# MainBoard.net
KiCad netlist of a schematic drawn in EAGLE
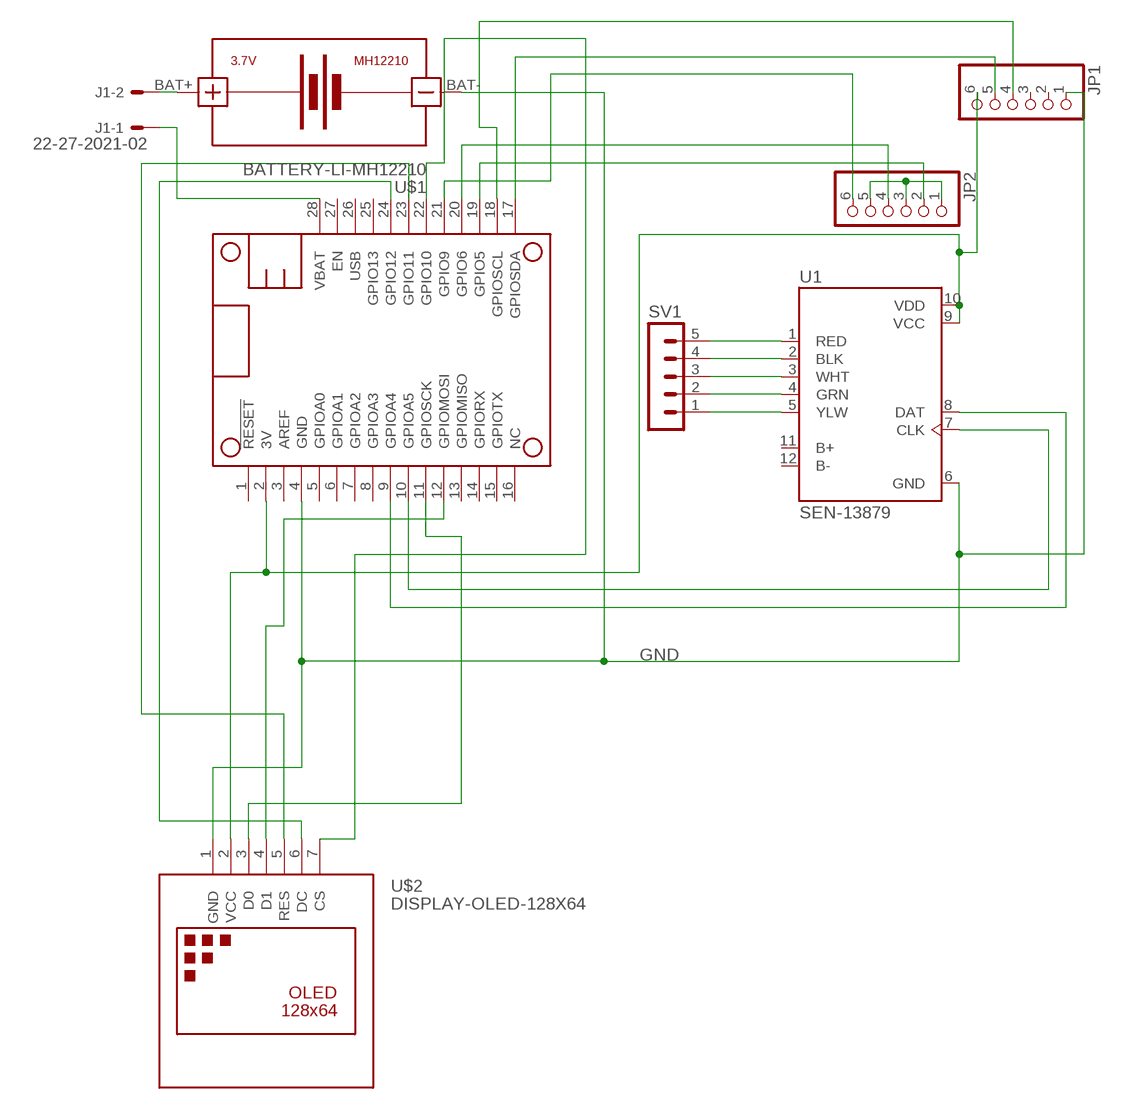
[diagram p0: schematic, sheet 1]

(export (version "E")
  (design (tool "Eeschema 10.0.6"))
  (components
    (comp (ref "J1")
      (value "22-27-2021-02")
      (footprint "eagle-import:6410-02")
      (fields (field (name "MF") "MOLEX"))
      (libsource (lib "eagle-import") (part "22-?-0227-2021"))
    )
    (comp (ref "JP1")
      (value "PINHD-1X6")
      (footprint "eagle-import:1X06")
      (libsource (lib "eagle-import") (part "PINHD-1X6"))
    )
    (comp (ref "JP2")
      (value "PINHD-1X6")
      (footprint "eagle-import:1X06")
      (libsource (lib "eagle-import") (part "PINHD-1X6"))
    )
    (comp (ref "MS1")
      (value "FEATHERWING_NODIM")
      (footprint "eagle-import:FEATHERWING_DIM")
      (libsource (lib "eagle-import") (part "FEATHERWING_NODIM"))
    )
    (comp (ref "SV1")
      (value "MA05-1")
      (footprint "eagle-import:MA05-1")
      (libsource (lib "eagle-import") (part "MA05-1"))
    )
    (comp (ref "U$1")
      (value "BATTERY-LI-MH12210")
      (footprint "eagle-import:BATTERY-LI-MH12210")
      (libsource (lib "eagle-import") (part "BATTERY-LI-MH12210"))
    )
    (comp (ref "U$2")
      (value "DISPLAY-OLED-128X64")
      (footprint "eagle-import:DISPLAY-OLED-128X64")
      (libsource (lib "eagle-import") (part "DISPLAY-OLED-128X64"))
    )
    (comp (ref "U1")
      (value "SEN-13879")
      (footprint "eagle-import:SPARKFUN_SEN-13879")
      (fields (field (name "MF") "SparkFun"))
      (libsource (lib "eagle-import") (part "SEN-13879"))
    )
  )
  (nets
    (net (code "1") (name "/GND") (class "Default")
      (node (ref "JP1") (pin "1") (pinfunction "1_1") (pintype "passive"))
      (node (ref "MS1") (pin "4") (pinfunction "GND_4") (pintype "power_in"))
      (node (ref "U$1") (pin "BAT-") (pinfunction "BAT-_BAT-") (pintype "power_in"))
      (node (ref "U$2") (pin "1") (pinfunction "GND_1") (pintype "power_in"))
      (node (ref "U1") (pin "6") (pinfunction "GND_6") (pintype "power_in"))
    )
    (net (code "2") (name "/USB") (class "Default")
      (node (ref "MS1") (pin "26") (pinfunction "USB_26") (pintype "power_in"))
    )
    (net (code "3") (name "Net-(J1A-S)") (class "Default")
      (node (ref "J1") (pin "1") (pinfunction "S_1") (pintype "passive"))
      (node (ref "MS1") (pin "28") (pinfunction "VBAT_28") (pintype "power_in"))
    )
    (net (code "4") (name "Net-(J1B-S)") (class "Default")
      (node (ref "J1") (pin "2") (pinfunction "S_2") (pintype "passive"))
      (node (ref "U$1") (pin "BAT+") (pinfunction "BAT+_BAT+") (pintype "power_in"))
    )
    (net (code "5") (name "Net-(JP2-Pad1)") (class "Default")
      (node (ref "JP2") (pin "1") (pinfunction "1_1") (pintype "passive"))
      (node (ref "JP2") (pin "3") (pinfunction "3_3") (pintype "passive"))
      (node (ref "JP2") (pin "5") (pinfunction "5_5") (pintype "passive"))
    )
    (net (code "6") (name "Net-(MS1-3V)") (class "Default")
      (node (ref "JP1") (pin "6") (pinfunction "6_6") (pintype "passive"))
      (node (ref "MS1") (pin "2") (pinfunction "3V_2") (pintype "power_in"))
      (node (ref "U$2") (pin "2") (pinfunction "VCC_2") (pintype "power_in"))
      (node (ref "U1") (pin "10") (pinfunction "VDD_10") (pintype "power_in"))
      (node (ref "U1") (pin "9") (pinfunction "VCC_9") (pintype "power_in"))
    )
    (net (code "7") (name "Net-(MS1-GPIO5)") (class "Default")
      (node (ref "JP2") (pin "2") (pinfunction "2_2") (pintype "passive"))
      (node (ref "MS1") (pin "19") (pinfunction "GPIO5_19") (pintype "bidirectional"))
    )
    (net (code "8") (name "Net-(MS1-GPIO6)") (class "Default")
      (node (ref "JP2") (pin "4") (pinfunction "4_4") (pintype "passive"))
      (node (ref "MS1") (pin "20") (pinfunction "GPIO6_20") (pintype "bidirectional"))
    )
    (net (code "9") (name "Net-(MS1-GPIO9)") (class "Default")
      (node (ref "JP2") (pin "6") (pinfunction "6_6") (pintype "passive"))
      (node (ref "MS1") (pin "21") (pinfunction "GPIO9_21") (pintype "bidirectional"))
    )
    (net (code "10") (name "Net-(MS1-GPIO10)") (class "Default")
      (node (ref "MS1") (pin "22") (pinfunction "GPIO10_22") (pintype "bidirectional"))
      (node (ref "U$2") (pin "7") (pinfunction "CS_7") (pintype "bidirectional"))
    )
    (net (code "11") (name "Net-(MS1-GPIO11)") (class "Default")
      (node (ref "MS1") (pin "23") (pinfunction "GPIO11_23") (pintype "bidirectional"))
      (node (ref "U$2") (pin "5") (pinfunction "RES_5") (pintype "bidirectional"))
    )
    (net (code "12") (name "Net-(MS1-GPIO12)") (class "Default")
      (node (ref "MS1") (pin "24") (pinfunction "GPIO12_24") (pintype "bidirectional"))
      (node (ref "U$2") (pin "6") (pinfunction "DC_6") (pintype "bidirectional"))
    )
    (net (code "13") (name "Net-(MS1-GPIOA4)") (class "Default")
      (node (ref "MS1") (pin "9") (pinfunction "GPIOA4_9") (pintype "bidirectional"))
      (node (ref "U1") (pin "8") (pinfunction "DAT_8") (pintype "output"))
    )
    (net (code "14") (name "Net-(MS1-GPIOA5)") (class "Default")
      (node (ref "MS1") (pin "10") (pinfunction "GPIOA5_10") (pintype "bidirectional"))
      (node (ref "U1") (pin "7") (pinfunction "CLK_7") (pintype "input"))
    )
    (net (code "15") (name "Net-(MS1-GPIOMOSI)") (class "Default")
      (node (ref "MS1") (pin "12") (pinfunction "GPIOMOSI_12") (pintype "bidirectional"))
      (node (ref "U$2") (pin "4") (pinfunction "D1_4") (pintype "bidirectional"))
    )
    (net (code "16") (name "Net-(MS1-GPIOSCK)") (class "Default")
      (node (ref "MS1") (pin "11") (pinfunction "GPIOSCK_11") (pintype "bidirectional"))
      (node (ref "U$2") (pin "3") (pinfunction "D0_3") (pintype "bidirectional"))
    )
    (net (code "17") (name "Net-(MS1-GPIOSCL)") (class "Default")
      (node (ref "JP1") (pin "4") (pinfunction "4_4") (pintype "passive"))
      (node (ref "MS1") (pin "18") (pinfunction "GPIOSCL_18") (pintype "bidirectional"))
    )
    (net (code "18") (name "Net-(MS1-GPIOSDA)") (class "Default")
      (node (ref "JP1") (pin "5") (pinfunction "5_5") (pintype "passive"))
      (node (ref "MS1") (pin "17") (pinfunction "GPIOSDA_17") (pintype "bidirectional"))
    )
    (net (code "19") (name "Net-(U1-BLK)") (class "Default")
      (node (ref "SV1") (pin "4") (pinfunction "4_4") (pintype "passive"))
      (node (ref "U1") (pin "2") (pinfunction "BLK_2") (pintype "bidirectional"))
    )
    (net (code "20") (name "Net-(U1-GRN)") (class "Default")
      (node (ref "SV1") (pin "2") (pinfunction "2_2") (pintype "passive"))
      (node (ref "U1") (pin "4") (pinfunction "GRN_4") (pintype "input"))
    )
    (net (code "21") (name "Net-(U1-RED)") (class "Default")
      (node (ref "SV1") (pin "5") (pinfunction "5_5") (pintype "passive"))
      (node (ref "U1") (pin "1") (pinfunction "RED_1") (pintype "bidirectional"))
    )
    (net (code "22") (name "Net-(U1-WHT)") (class "Default")
      (node (ref "SV1") (pin "3") (pinfunction "3_3") (pintype "passive"))
      (node (ref "U1") (pin "3") (pinfunction "WHT_3") (pintype "input"))
    )
    (net (code "23") (name "Net-(U1-YLW)") (class "Default")
      (node (ref "SV1") (pin "1") (pinfunction "1_1") (pintype "passive"))
      (node (ref "U1") (pin "5") (pinfunction "YLW_5") (pintype "bidirectional"))
    )
    (net (code "24") (name "unconnected-(JP1-Pad2)") (class "Default")
      (node (ref "JP1") (pin "2") (pinfunction "2_2") (pintype "passive"))
    )
    (net (code "25") (name "unconnected-(JP1-Pad3)") (class "Default")
      (node (ref "JP1") (pin "3") (pinfunction "3_3") (pintype "passive"))
    )
    (net (code "26") (name "unconnected-(MS1-AREF-Pad3)") (class "Default")
      (node (ref "MS1") (pin "3") (pinfunction "AREF_3") (pintype "passive"))
    )
    (net (code "27") (name "unconnected-(MS1-EN-Pad27)") (class "Default")
      (node (ref "MS1") (pin "27") (pinfunction "EN_27") (pintype "passive"))
    )
    (net (code "28") (name "unconnected-(MS1-GPIO13-Pad25)") (class "Default")
      (node (ref "MS1") (pin "25") (pinfunction "GPIO13_25") (pintype "bidirectional"))
    )
    (net (code "29") (name "unconnected-(MS1-GPIOA0-Pad5)") (class "Default")
      (node (ref "MS1") (pin "5") (pinfunction "GPIOA0_5") (pintype "bidirectional"))
    )
    (net (code "30") (name "unconnected-(MS1-GPIOA1-Pad6)") (class "Default")
      (node (ref "MS1") (pin "6") (pinfunction "GPIOA1_6") (pintype "bidirectional"))
    )
    (net (code "31") (name "unconnected-(MS1-GPIOA2-Pad7)") (class "Default")
      (node (ref "MS1") (pin "7") (pinfunction "GPIOA2_7") (pintype "bidirectional"))
    )
    (net (code "32") (name "unconnected-(MS1-GPIOA3-Pad8)") (class "Default")
      (node (ref "MS1") (pin "8") (pinfunction "GPIOA3_8") (pintype "bidirectional"))
    )
    (net (code "33") (name "unconnected-(MS1-GPIOMISO-Pad13)") (class "Default")
      (node (ref "MS1") (pin "13") (pinfunction "GPIOMISO_13") (pintype "bidirectional"))
    )
    (net (code "34") (name "unconnected-(MS1-GPIORX-Pad14)") (class "Default")
      (node (ref "MS1") (pin "14") (pinfunction "GPIORX_14") (pintype "bidirectional"))
    )
    (net (code "35") (name "unconnected-(MS1-GPIOTX-Pad15)") (class "Default")
      (node (ref "MS1") (pin "15") (pinfunction "GPIOTX_15") (pintype "bidirectional"))
    )
    (net (code "36") (name "unconnected-(MS1-NC-Pad16)") (class "Default")
      (node (ref "MS1") (pin "16") (pinfunction "NC_16") (pintype "passive"))
    )
    (net (code "37") (name "unconnected-(MS1-~{RESET}-Pad1)") (class "Default")
      (node (ref "MS1") (pin "1") (pinfunction "~{RESET}_1") (pintype "input"))
    )
    (net (code "38") (name "unconnected-(U1-B+-Pad11)") (class "Default")
      (node (ref "U1") (pin "11") (pinfunction "B+_11") (pintype "input"))
    )
    (net (code "39") (name "unconnected-(U1-B--Pad12)") (class "Default")
      (node (ref "U1") (pin "12") (pinfunction "B-_12") (pintype "input"))
    )
  )
)
